# MacroBoard.net
KiCad netlist of a schematic drawn in EAGLE
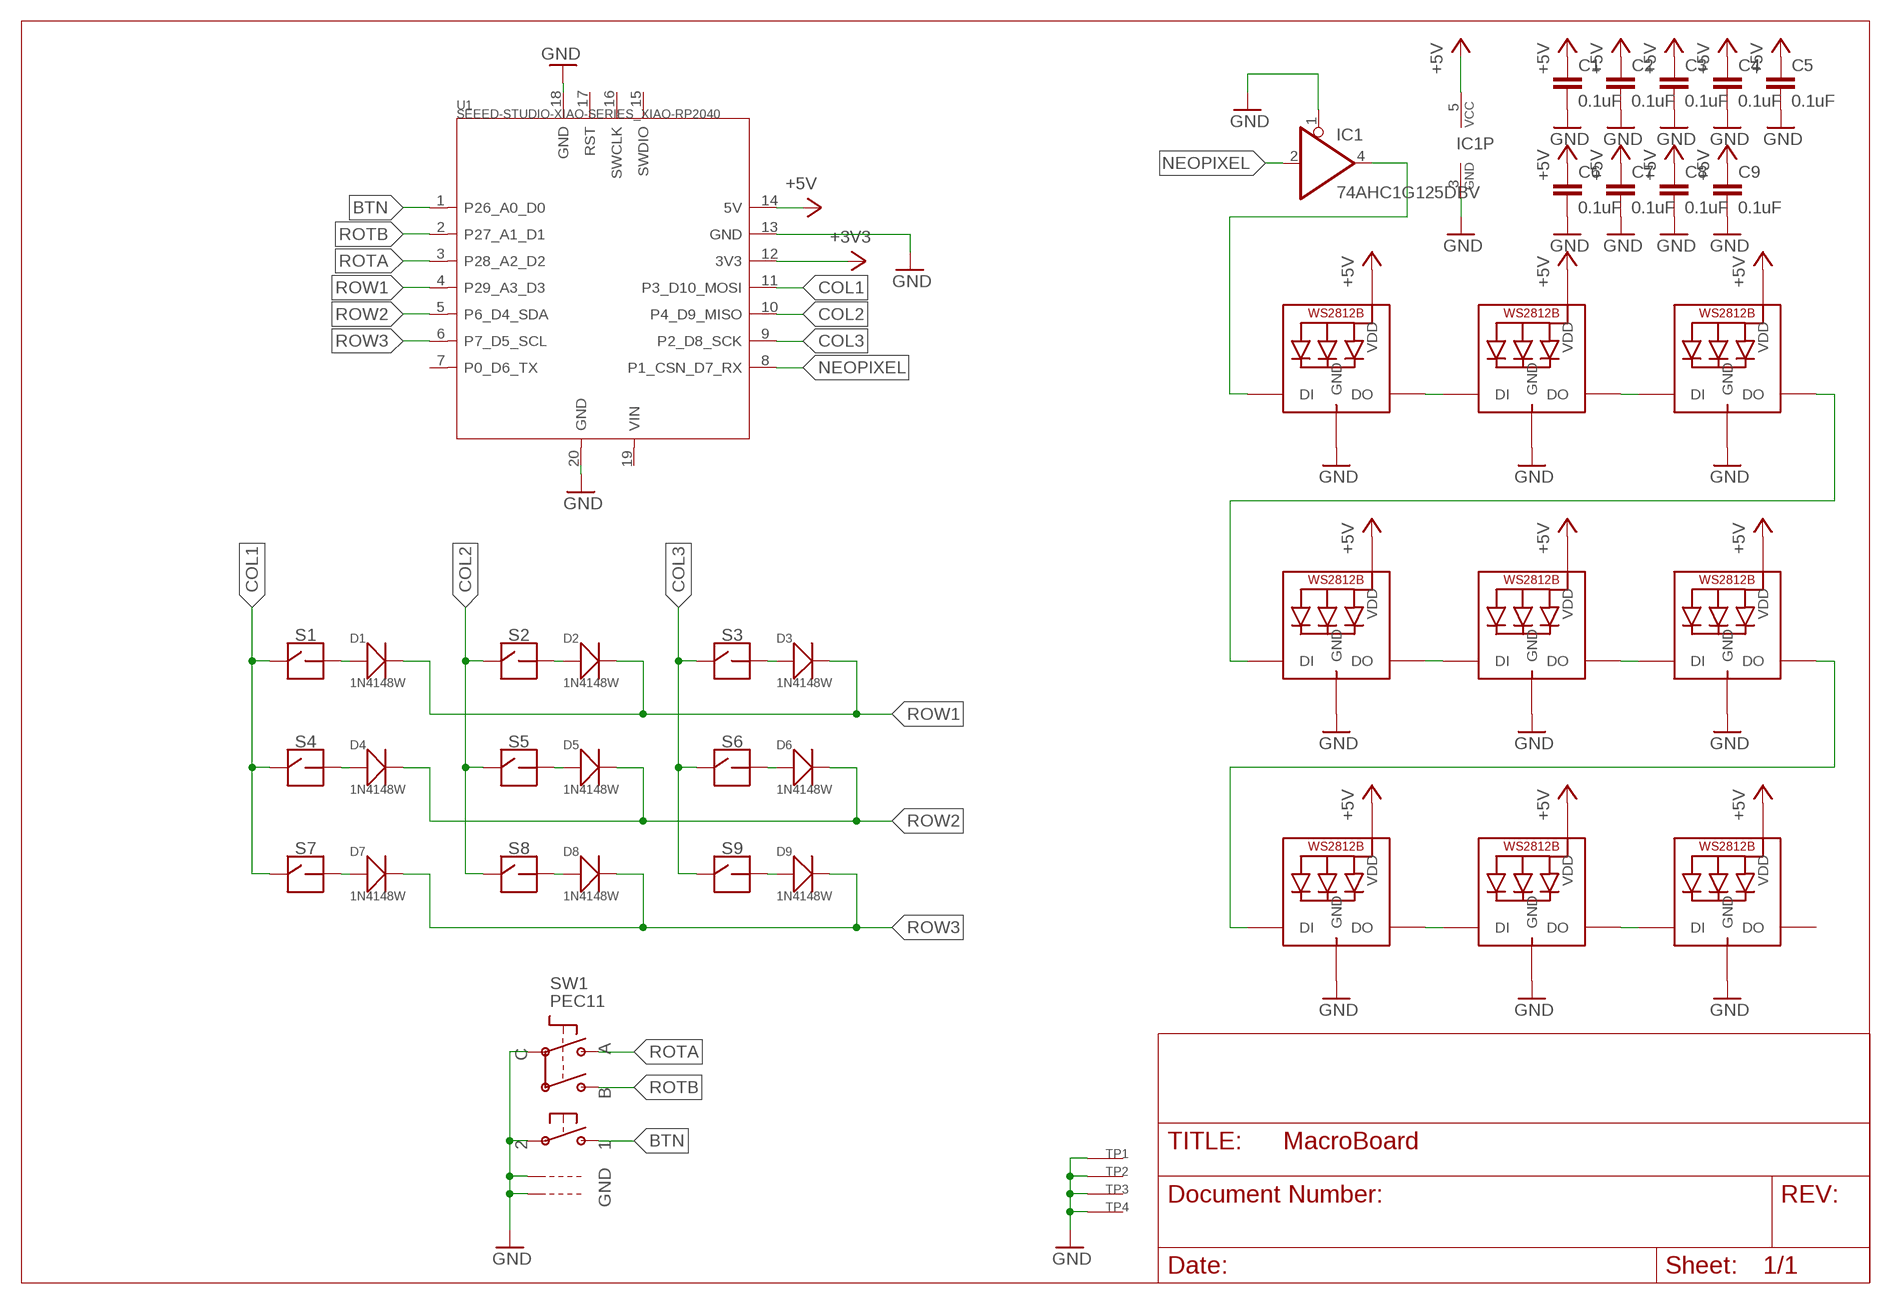
[diagram p0: schematic, sheet 1]

(export (version "E")
  (design (tool "Eeschema 10.0.6"))
  (components
    (comp (ref "C1")
      (value "0.1uF")
      (footprint "eagle-import:C0805K")
      (libsource (lib "eagle-import") (part "C-EUC0805K"))
    )
    (comp (ref "C2")
      (value "0.1uF")
      (footprint "eagle-import:C0805K")
      (libsource (lib "eagle-import") (part "C-EUC0805K"))
    )
    (comp (ref "C3")
      (value "0.1uF")
      (footprint "eagle-import:C0805K")
      (libsource (lib "eagle-import") (part "C-EUC0805K"))
    )
    (comp (ref "C4")
      (value "0.1uF")
      (footprint "eagle-import:C0805K")
      (libsource (lib "eagle-import") (part "C-EUC0805K"))
    )
    (comp (ref "C5")
      (value "0.1uF")
      (footprint "eagle-import:C0805K")
      (libsource (lib "eagle-import") (part "C-EUC0805K"))
    )
    (comp (ref "C6")
      (value "0.1uF")
      (footprint "eagle-import:C0805K")
      (libsource (lib "eagle-import") (part "C-EUC0805K"))
    )
    (comp (ref "C7")
      (value "0.1uF")
      (footprint "eagle-import:C0805K")
      (libsource (lib "eagle-import") (part "C-EUC0805K"))
    )
    (comp (ref "C8")
      (value "0.1uF")
      (footprint "eagle-import:C0805K")
      (libsource (lib "eagle-import") (part "C-EUC0805K"))
    )
    (comp (ref "C9")
      (value "0.1uF")
      (footprint "eagle-import:C0805K")
      (libsource (lib "eagle-import") (part "C-EUC0805K"))
    )
    (comp (ref "D1")
      (value "1N4148W")
      (footprint "eagle-import:SOD-123")
      (fields (field (name "MPN") "B5819W"))
      (libsource (lib "eagle-import") (part "SMD-DIODE-SCHOTTKY-20V-1A(SOD-123)"))
    )
    (comp (ref "D2")
      (value "1N4148W")
      (footprint "eagle-import:SOD-123")
      (fields (field (name "MPN") "B5819W"))
      (libsource (lib "eagle-import") (part "SMD-DIODE-SCHOTTKY-20V-1A(SOD-123)"))
    )
    (comp (ref "D3")
      (value "1N4148W")
      (footprint "eagle-import:SOD-123")
      (fields (field (name "MPN") "B5819W"))
      (libsource (lib "eagle-import") (part "SMD-DIODE-SCHOTTKY-20V-1A(SOD-123)"))
    )
    (comp (ref "D4")
      (value "1N4148W")
      (footprint "eagle-import:SOD-123")
      (fields (field (name "MPN") "B5819W"))
      (libsource (lib "eagle-import") (part "SMD-DIODE-SCHOTTKY-20V-1A(SOD-123)"))
    )
    (comp (ref "D5")
      (value "1N4148W")
      (footprint "eagle-import:SOD-123")
      (fields (field (name "MPN") "B5819W"))
      (libsource (lib "eagle-import") (part "SMD-DIODE-SCHOTTKY-20V-1A(SOD-123)"))
    )
    (comp (ref "D6")
      (value "1N4148W")
      (footprint "eagle-import:SOD-123")
      (fields (field (name "MPN") "B5819W"))
      (libsource (lib "eagle-import") (part "SMD-DIODE-SCHOTTKY-20V-1A(SOD-123)"))
    )
    (comp (ref "D7")
      (value "1N4148W")
      (footprint "eagle-import:SOD-123")
      (fields (field (name "MPN") "B5819W"))
      (libsource (lib "eagle-import") (part "SMD-DIODE-SCHOTTKY-20V-1A(SOD-123)"))
    )
    (comp (ref "D8")
      (value "1N4148W")
      (footprint "eagle-import:SOD-123")
      (fields (field (name "MPN") "B5819W"))
      (libsource (lib "eagle-import") (part "SMD-DIODE-SCHOTTKY-20V-1A(SOD-123)"))
    )
    (comp (ref "D9")
      (value "1N4148W")
      (footprint "eagle-import:SOD-123")
      (fields (field (name "MPN") "B5819W"))
      (libsource (lib "eagle-import") (part "SMD-DIODE-SCHOTTKY-20V-1A(SOD-123)"))
    )
    (comp (ref "IC1")
      (value "74AHC1G125DBV")
      (footprint "eagle-import:SOT23-5")
      (fields (field (name "SPICEPREFIX") "J"))
      (libsource (lib "eagle-import") (part "741G125DBVAHC"))
    )
    (comp (ref "LED1")
      (value "MICROBUILDER_WS2812B_SK6812E")
      (footprint "eagle-import:MICROBUILDER_NEO3535_REVERSE")
      (libsource (lib "eagle-import") (part "MICROBUILDER_WS2812B_SK6812E"))
    )
    (comp (ref "LED2")
      (value "MICROBUILDER_WS2812B_SK6812E")
      (footprint "eagle-import:MICROBUILDER_NEO3535_REVERSE")
      (libsource (lib "eagle-import") (part "MICROBUILDER_WS2812B_SK6812E"))
    )
    (comp (ref "LED3")
      (value "MICROBUILDER_WS2812B_SK6812E")
      (footprint "eagle-import:MICROBUILDER_NEO3535_REVERSE")
      (libsource (lib "eagle-import") (part "MICROBUILDER_WS2812B_SK6812E"))
    )
    (comp (ref "LED4")
      (value "MICROBUILDER_WS2812B_SK6812E")
      (footprint "eagle-import:MICROBUILDER_NEO3535_REVERSE")
      (libsource (lib "eagle-import") (part "MICROBUILDER_WS2812B_SK6812E"))
    )
    (comp (ref "LED5")
      (value "MICROBUILDER_WS2812B_SK6812E")
      (footprint "eagle-import:MICROBUILDER_NEO3535_REVERSE")
      (libsource (lib "eagle-import") (part "MICROBUILDER_WS2812B_SK6812E"))
    )
    (comp (ref "LED6")
      (value "MICROBUILDER_WS2812B_SK6812E")
      (footprint "eagle-import:MICROBUILDER_NEO3535_REVERSE")
      (libsource (lib "eagle-import") (part "MICROBUILDER_WS2812B_SK6812E"))
    )
    (comp (ref "LED7")
      (value "MICROBUILDER_WS2812B_SK6812E")
      (footprint "eagle-import:MICROBUILDER_NEO3535_REVERSE")
      (libsource (lib "eagle-import") (part "MICROBUILDER_WS2812B_SK6812E"))
    )
    (comp (ref "LED8")
      (value "MICROBUILDER_WS2812B_SK6812E")
      (footprint "eagle-import:MICROBUILDER_NEO3535_REVERSE")
      (libsource (lib "eagle-import") (part "MICROBUILDER_WS2812B_SK6812E"))
    )
    (comp (ref "LED9")
      (value "MICROBUILDER_WS2812B_SK6812E")
      (footprint "eagle-import:MICROBUILDER_NEO3535_REVERSE")
      (libsource (lib "eagle-import") (part "MICROBUILDER_WS2812B_SK6812E"))
    )
    (comp (ref "S1")
      (value "SOCKET")
      (footprint "eagle-import:ADAFRUIT_ELECTROMECH_KAILH_SOCKET")
      (libsource (lib "eagle-import") (part "ADAFRUIT_ELECTROMECH_KBD_SWITCH_KAILH_SOCKETBOX_JADE_KAILH_SOCKET"))
    )
    (comp (ref "S2")
      (value "SOCKET")
      (footprint "eagle-import:ADAFRUIT_ELECTROMECH_KAILH_SOCKET")
      (libsource (lib "eagle-import") (part "ADAFRUIT_ELECTROMECH_KBD_SWITCH_KAILH_SOCKETBOX_JADE_KAILH_SOCKET"))
    )
    (comp (ref "S3")
      (value "SOCKET")
      (footprint "eagle-import:ADAFRUIT_ELECTROMECH_KAILH_SOCKET")
      (libsource (lib "eagle-import") (part "ADAFRUIT_ELECTROMECH_KBD_SWITCH_KAILH_SOCKETBOX_JADE_KAILH_SOCKET"))
    )
    (comp (ref "S4")
      (value "SOCKET")
      (footprint "eagle-import:ADAFRUIT_ELECTROMECH_KAILH_SOCKET")
      (libsource (lib "eagle-import") (part "ADAFRUIT_ELECTROMECH_KBD_SWITCH_KAILH_SOCKETBOX_JADE_KAILH_SOCKET"))
    )
    (comp (ref "S5")
      (value "SOCKET")
      (footprint "eagle-import:ADAFRUIT_ELECTROMECH_KAILH_SOCKET")
      (libsource (lib "eagle-import") (part "ADAFRUIT_ELECTROMECH_KBD_SWITCH_KAILH_SOCKETBOX_JADE_KAILH_SOCKET"))
    )
    (comp (ref "S6")
      (value "SOCKET")
      (footprint "eagle-import:ADAFRUIT_ELECTROMECH_KAILH_SOCKET")
      (libsource (lib "eagle-import") (part "ADAFRUIT_ELECTROMECH_KBD_SWITCH_KAILH_SOCKETBOX_JADE_KAILH_SOCKET"))
    )
    (comp (ref "S7")
      (value "SOCKET")
      (footprint "eagle-import:ADAFRUIT_ELECTROMECH_KAILH_SOCKET")
      (libsource (lib "eagle-import") (part "ADAFRUIT_ELECTROMECH_KBD_SWITCH_KAILH_SOCKETBOX_JADE_KAILH_SOCKET"))
    )
    (comp (ref "S8")
      (value "SOCKET")
      (footprint "eagle-import:ADAFRUIT_ELECTROMECH_KAILH_SOCKET")
      (libsource (lib "eagle-import") (part "ADAFRUIT_ELECTROMECH_KBD_SWITCH_KAILH_SOCKETBOX_JADE_KAILH_SOCKET"))
    )
    (comp (ref "S9")
      (value "SOCKET")
      (footprint "eagle-import:ADAFRUIT_ELECTROMECH_KAILH_SOCKET")
      (libsource (lib "eagle-import") (part "ADAFRUIT_ELECTROMECH_KBD_SWITCH_KAILH_SOCKETBOX_JADE_KAILH_SOCKET"))
    )
    (comp (ref "SW1")
      (value "PEC11")
      (footprint "eagle-import:ADAFRUIT_ELECTROMECH_PEC11+SWITCH")
      (libsource (lib "eagle-import") (part "ADAFRUIT_ELECTROMECH_ENCODER_PLUS_SWITCH_PEC11_BOURNS"))
    )
    (comp (ref "TP1")
      (value "SEWTAP_SMTNUTM3")
      (footprint "eagle-import:SMT_NUT_3MM")
      (libsource (lib "eagle-import") (part "SEWTAP_SMTNUTM3"))
    )
    (comp (ref "TP2")
      (value "SEWTAP_SMTNUTM3")
      (footprint "eagle-import:SMT_NUT_3MM")
      (libsource (lib "eagle-import") (part "SEWTAP_SMTNUTM3"))
    )
    (comp (ref "TP3")
      (value "SEWTAP_SMTNUTM3")
      (footprint "eagle-import:SMT_NUT_3MM")
      (libsource (lib "eagle-import") (part "SEWTAP_SMTNUTM3"))
    )
    (comp (ref "TP4")
      (value "SEWTAP_SMTNUTM3")
      (footprint "eagle-import:SMT_NUT_3MM")
      (libsource (lib "eagle-import") (part "SEWTAP_SMTNUTM3"))
    )
    (comp (ref "U1")
      (value "SEEED-STUDIO-XIAO-SERIES_XIAO-RP2040")
      (footprint "eagle-import:SEEED-STUDIO-XIAO-SERIES_XIAO-SAMD21_RP2040-MODULE14P-2.54-21X17.8MM")
      (libsource (lib "eagle-import") (part "SEEED-STUDIO-XIAO-SERIES_XIAO-RP2040"))
    )
  )
  (nets
    (net (code "1") (name "+3V3") (class "Default")
      (node (ref "U1") (pin "12") (pinfunction "3V3_12") (pintype "bidirectional"))
    )
    (net (code "2") (name "+5V") (class "Default")
      (node (ref "C1") (pin "1") (pinfunction "1_1") (pintype "passive"))
      (node (ref "C2") (pin "1") (pinfunction "1_1") (pintype "passive"))
      (node (ref "C3") (pin "1") (pinfunction "1_1") (pintype "passive"))
      (node (ref "C4") (pin "1") (pinfunction "1_1") (pintype "passive"))
      (node (ref "C5") (pin "1") (pinfunction "1_1") (pintype "passive"))
      (node (ref "C6") (pin "1") (pinfunction "1_1") (pintype "passive"))
      (node (ref "C7") (pin "1") (pinfunction "1_1") (pintype "passive"))
      (node (ref "C8") (pin "1") (pinfunction "1_1") (pintype "passive"))
      (node (ref "C9") (pin "1") (pinfunction "1_1") (pintype "passive"))
      (node (ref "IC1") (pin "5") (pinfunction "VCC_5") (pintype "power_in"))
      (node (ref "LED1") (pin "1-VDD") (pinfunction "VDD_1-VDD") (pintype "power_in"))
      (node (ref "LED2") (pin "1-VDD") (pinfunction "VDD_1-VDD") (pintype "power_in"))
      (node (ref "LED3") (pin "1-VDD") (pinfunction "VDD_1-VDD") (pintype "power_in"))
      (node (ref "LED4") (pin "1-VDD") (pinfunction "VDD_1-VDD") (pintype "power_in"))
      (node (ref "LED5") (pin "1-VDD") (pinfunction "VDD_1-VDD") (pintype "power_in"))
      (node (ref "LED6") (pin "1-VDD") (pinfunction "VDD_1-VDD") (pintype "power_in"))
      (node (ref "LED7") (pin "1-VDD") (pinfunction "VDD_1-VDD") (pintype "power_in"))
      (node (ref "LED8") (pin "1-VDD") (pinfunction "VDD_1-VDD") (pintype "power_in"))
      (node (ref "LED9") (pin "1-VDD") (pinfunction "VDD_1-VDD") (pintype "power_in"))
      (node (ref "U1") (pin "14") (pinfunction "5V_14") (pintype "bidirectional"))
    )
    (net (code "3") (name "BTN") (class "Default")
      (node (ref "SW1") (pin "P$1") (pinfunction "P$1_P$1") (pintype "passive"))
      (node (ref "U1") (pin "1") (pinfunction "P26_A0_D0_1") (pintype "bidirectional"))
    )
    (net (code "4") (name "COL1") (class "Default")
      (node (ref "S1") (pin "1") (pinfunction "1_1") (pintype "passive"))
      (node (ref "S4") (pin "1") (pinfunction "1_1") (pintype "passive"))
      (node (ref "S7") (pin "1") (pinfunction "1_1") (pintype "passive"))
      (node (ref "U1") (pin "11") (pinfunction "P3_D10_MOSI_11") (pintype "bidirectional"))
    )
    (net (code "5") (name "COL2") (class "Default")
      (node (ref "S2") (pin "1") (pinfunction "1_1") (pintype "passive"))
      (node (ref "S5") (pin "1") (pinfunction "1_1") (pintype "passive"))
      (node (ref "S8") (pin "1") (pinfunction "1_1") (pintype "passive"))
      (node (ref "U1") (pin "10") (pinfunction "P4_D9_MISO_10") (pintype "bidirectional"))
    )
    (net (code "6") (name "COL3") (class "Default")
      (node (ref "S3") (pin "1") (pinfunction "1_1") (pintype "passive"))
      (node (ref "S6") (pin "1") (pinfunction "1_1") (pintype "passive"))
      (node (ref "S9") (pin "1") (pinfunction "1_1") (pintype "passive"))
      (node (ref "U1") (pin "9") (pinfunction "P2_D8_SCK_9") (pintype "bidirectional"))
    )
    (net (code "7") (name "GND") (class "Default")
      (node (ref "C1") (pin "2") (pinfunction "2_2") (pintype "passive"))
      (node (ref "C2") (pin "2") (pinfunction "2_2") (pintype "passive"))
      (node (ref "C3") (pin "2") (pinfunction "2_2") (pintype "passive"))
      (node (ref "C4") (pin "2") (pinfunction "2_2") (pintype "passive"))
      (node (ref "C5") (pin "2") (pinfunction "2_2") (pintype "passive"))
      (node (ref "C6") (pin "2") (pinfunction "2_2") (pintype "passive"))
      (node (ref "C7") (pin "2") (pinfunction "2_2") (pintype "passive"))
      (node (ref "C8") (pin "2") (pinfunction "2_2") (pintype "passive"))
      (node (ref "C9") (pin "2") (pinfunction "2_2") (pintype "passive"))
      (node (ref "IC1") (pin "1") (pinfunction "OE_1") (pintype "input"))
      (node (ref "IC1") (pin "3") (pinfunction "GND_3") (pintype "power_in"))
      (node (ref "LED1") (pin "3-GND") (pinfunction "GND_3-GND") (pintype "power_in"))
      (node (ref "LED2") (pin "3-GND") (pinfunction "GND_3-GND") (pintype "power_in"))
      (node (ref "LED3") (pin "3-GND") (pinfunction "GND_3-GND") (pintype "power_in"))
      (node (ref "LED4") (pin "3-GND") (pinfunction "GND_3-GND") (pintype "power_in"))
      (node (ref "LED5") (pin "3-GND") (pinfunction "GND_3-GND") (pintype "power_in"))
      (node (ref "LED6") (pin "3-GND") (pinfunction "GND_3-GND") (pintype "power_in"))
      (node (ref "LED7") (pin "3-GND") (pinfunction "GND_3-GND") (pintype "power_in"))
      (node (ref "LED8") (pin "3-GND") (pinfunction "GND_3-GND") (pintype "power_in"))
      (node (ref "LED9") (pin "3-GND") (pinfunction "GND_3-GND") (pintype "power_in"))
      (node (ref "SW1") (pin "P$2") (pinfunction "P$2_P$2") (pintype "passive"))
      (node (ref "SW1") (pin "P$C") (pinfunction "P$C_P$C") (pintype "passive"))
      (node (ref "SW1") (pin "P$GND1") (pinfunction "P$GND1_P$GND1") (pintype "passive"))
      (node (ref "SW1") (pin "P$GND2") (pinfunction "P$GND2_P$GND2") (pintype "passive"))
      (node (ref "TP1") (pin "P$1") (pinfunction "SEW_P$1") (pintype "bidirectional"))
      (node (ref "TP2") (pin "P$1") (pinfunction "SEW_P$1") (pintype "bidirectional"))
      (node (ref "TP3") (pin "P$1") (pinfunction "SEW_P$1") (pintype "bidirectional"))
      (node (ref "TP4") (pin "P$1") (pinfunction "SEW_P$1") (pintype "bidirectional"))
      (node (ref "U1") (pin "13") (pinfunction "GND_13") (pintype "bidirectional"))
      (node (ref "U1") (pin "18") (pinfunction "GND_18") (pintype "bidirectional"))
      (node (ref "U1") (pin "20") (pinfunction "GND_20") (pintype "bidirectional"))
    )
    (net (code "8") (name "NEOPIXEL") (class "Default")
      (node (ref "IC1") (pin "2") (pinfunction "I_2") (pintype "input"))
      (node (ref "U1") (pin "8") (pinfunction "P1_CSN_D7_RX_8") (pintype "bidirectional"))
    )
    (net (code "9") (name "Net-(D1-Pad+)") (class "Default")
      (node (ref "D1") (pin "+") (pinfunction "+_+") (pintype "passive"))
      (node (ref "S1") (pin "2") (pinfunction "2_2") (pintype "passive"))
    )
    (net (code "10") (name "Net-(D2-Pad+)") (class "Default")
      (node (ref "D2") (pin "+") (pinfunction "+_+") (pintype "passive"))
      (node (ref "S2") (pin "2") (pinfunction "2_2") (pintype "passive"))
    )
    (net (code "11") (name "Net-(D3-Pad+)") (class "Default")
      (node (ref "D3") (pin "+") (pinfunction "+_+") (pintype "passive"))
      (node (ref "S3") (pin "2") (pinfunction "2_2") (pintype "passive"))
    )
    (net (code "12") (name "Net-(D4-Pad+)") (class "Default")
      (node (ref "D4") (pin "+") (pinfunction "+_+") (pintype "passive"))
      (node (ref "S4") (pin "2") (pinfunction "2_2") (pintype "passive"))
    )
    (net (code "13") (name "Net-(D5-Pad+)") (class "Default")
      (node (ref "D5") (pin "+") (pinfunction "+_+") (pintype "passive"))
      (node (ref "S5") (pin "2") (pinfunction "2_2") (pintype "passive"))
    )
    (net (code "14") (name "Net-(D6-Pad+)") (class "Default")
      (node (ref "D6") (pin "+") (pinfunction "+_+") (pintype "passive"))
      (node (ref "S6") (pin "2") (pinfunction "2_2") (pintype "passive"))
    )
    (net (code "15") (name "Net-(D7-Pad+)") (class "Default")
      (node (ref "D7") (pin "+") (pinfunction "+_+") (pintype "passive"))
      (node (ref "S7") (pin "2") (pinfunction "2_2") (pintype "passive"))
    )
    (net (code "16") (name "Net-(D8-Pad+)") (class "Default")
      (node (ref "D8") (pin "+") (pinfunction "+_+") (pintype "passive"))
      (node (ref "S8") (pin "2") (pinfunction "2_2") (pintype "passive"))
    )
    (net (code "17") (name "Net-(D9-Pad+)") (class "Default")
      (node (ref "D9") (pin "+") (pinfunction "+_+") (pintype "passive"))
      (node (ref "S9") (pin "2") (pinfunction "2_2") (pintype "passive"))
    )
    (net (code "18") (name "Net-(IC1A-O)") (class "Default")
      (node (ref "IC1") (pin "4") (pinfunction "O_4") (pintype "tri_state"))
      (node (ref "LED1") (pin "4-DIN") (pinfunction "DI_4-DIN") (pintype "input"))
    )
    (net (code "19") (name "Net-(LED1-DO)") (class "Default")
      (node (ref "LED1") (pin "2-DOUT") (pinfunction "DO_2-DOUT") (pintype "output"))
      (node (ref "LED2") (pin "4-DIN") (pinfunction "DI_4-DIN") (pintype "input"))
    )
    (net (code "20") (name "Net-(LED2-DO)") (class "Default")
      (node (ref "LED2") (pin "2-DOUT") (pinfunction "DO_2-DOUT") (pintype "output"))
      (node (ref "LED3") (pin "4-DIN") (pinfunction "DI_4-DIN") (pintype "input"))
    )
    (net (code "21") (name "Net-(LED3-DO)") (class "Default")
      (node (ref "LED3") (pin "2-DOUT") (pinfunction "DO_2-DOUT") (pintype "output"))
      (node (ref "LED4") (pin "4-DIN") (pinfunction "DI_4-DIN") (pintype "input"))
    )
    (net (code "22") (name "Net-(LED4-DO)") (class "Default")
      (node (ref "LED4") (pin "2-DOUT") (pinfunction "DO_2-DOUT") (pintype "output"))
      (node (ref "LED5") (pin "4-DIN") (pinfunction "DI_4-DIN") (pintype "input"))
    )
    (net (code "23") (name "Net-(LED5-DO)") (class "Default")
      (node (ref "LED5") (pin "2-DOUT") (pinfunction "DO_2-DOUT") (pintype "output"))
      (node (ref "LED6") (pin "4-DIN") (pinfunction "DI_4-DIN") (pintype "input"))
    )
    (net (code "24") (name "Net-(LED6-DO)") (class "Default")
      (node (ref "LED6") (pin "2-DOUT") (pinfunction "DO_2-DOUT") (pintype "output"))
      (node (ref "LED7") (pin "4-DIN") (pinfunction "DI_4-DIN") (pintype "input"))
    )
    (net (code "25") (name "Net-(LED7-DO)") (class "Default")
      (node (ref "LED7") (pin "2-DOUT") (pinfunction "DO_2-DOUT") (pintype "output"))
      (node (ref "LED8") (pin "4-DIN") (pinfunction "DI_4-DIN") (pintype "input"))
    )
    (net (code "26") (name "Net-(LED8-DO)") (class "Default")
      (node (ref "LED8") (pin "2-DOUT") (pinfunction "DO_2-DOUT") (pintype "output"))
      (node (ref "LED9") (pin "4-DIN") (pinfunction "DI_4-DIN") (pintype "input"))
    )
    (net (code "27") (name "ROTA") (class "Default")
      (node (ref "SW1") (pin "P$A") (pinfunction "P$A_P$A") (pintype "passive"))
      (node (ref "U1") (pin "3") (pinfunction "P28_A2_D2_3") (pintype "bidirectional"))
    )
    (net (code "28") (name "ROTB") (class "Default")
      (node (ref "SW1") (pin "P$B") (pinfunction "P$B_P$B") (pintype "passive"))
      (node (ref "U1") (pin "2") (pinfunction "P27_A1_D1_2") (pintype "bidirectional"))
    )
    (net (code "29") (name "ROW1") (class "Default")
      (node (ref "D1") (pin "-") (pinfunction "-_-") (pintype "passive"))
      (node (ref "D2") (pin "-") (pinfunction "-_-") (pintype "passive"))
      (node (ref "D3") (pin "-") (pinfunction "-_-") (pintype "passive"))
      (node (ref "U1") (pin "4") (pinfunction "P29_A3_D3_4") (pintype "bidirectional"))
    )
    (net (code "30") (name "ROW2") (class "Default")
      (node (ref "D4") (pin "-") (pinfunction "-_-") (pintype "passive"))
      (node (ref "D5") (pin "-") (pinfunction "-_-") (pintype "passive"))
      (node (ref "D6") (pin "-") (pinfunction "-_-") (pintype "passive"))
      (node (ref "U1") (pin "5") (pinfunction "P6_D4_SDA_5") (pintype "bidirectional"))
    )
    (net (code "31") (name "ROW3") (class "Default")
      (node (ref "D7") (pin "-") (pinfunction "-_-") (pintype "passive"))
      (node (ref "D8") (pin "-") (pinfunction "-_-") (pintype "passive"))
      (node (ref "D9") (pin "-") (pinfunction "-_-") (pintype "passive"))
      (node (ref "U1") (pin "6") (pinfunction "P7_D5_SCL_6") (pintype "bidirectional"))
    )
    (net (code "32") (name "unconnected-(LED9-DO-Pad2-DOUT)") (class "Default")
      (node (ref "LED9") (pin "2-DOUT") (pinfunction "DO_2-DOUT") (pintype "output"))
    )
    (net (code "33") (name "unconnected-(U1-P0_D6_TX-Pad7)") (class "Default")
      (node (ref "U1") (pin "7") (pinfunction "P0_D6_TX_7") (pintype "bidirectional"))
    )
    (net (code "34") (name "unconnected-(U1-RST-Pad17)") (class "Default")
      (node (ref "U1") (pin "17") (pinfunction "RST_17") (pintype "bidirectional"))
    )
    (net (code "35") (name "unconnected-(U1-SWCLK-Pad16)") (class "Default")
      (node (ref "U1") (pin "16") (pinfunction "SWCLK_16") (pintype "bidirectional"))
    )
    (net (code "36") (name "unconnected-(U1-SWDIO-Pad15)") (class "Default")
      (node (ref "U1") (pin "15") (pinfunction "SWDIO_15") (pintype "bidirectional"))
    )
    (net (code "37") (name "unconnected-(U1-VIN-Pad19)") (class "Default")
      (node (ref "U1") (pin "19") (pinfunction "VIN_19") (pintype "bidirectional"))
    )
  )
)
